# Openbook.net
KiCad netlist of a schematic drawn in EAGLE
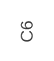
[diagram p0: schematic, sheet 1, part 1 of 2]
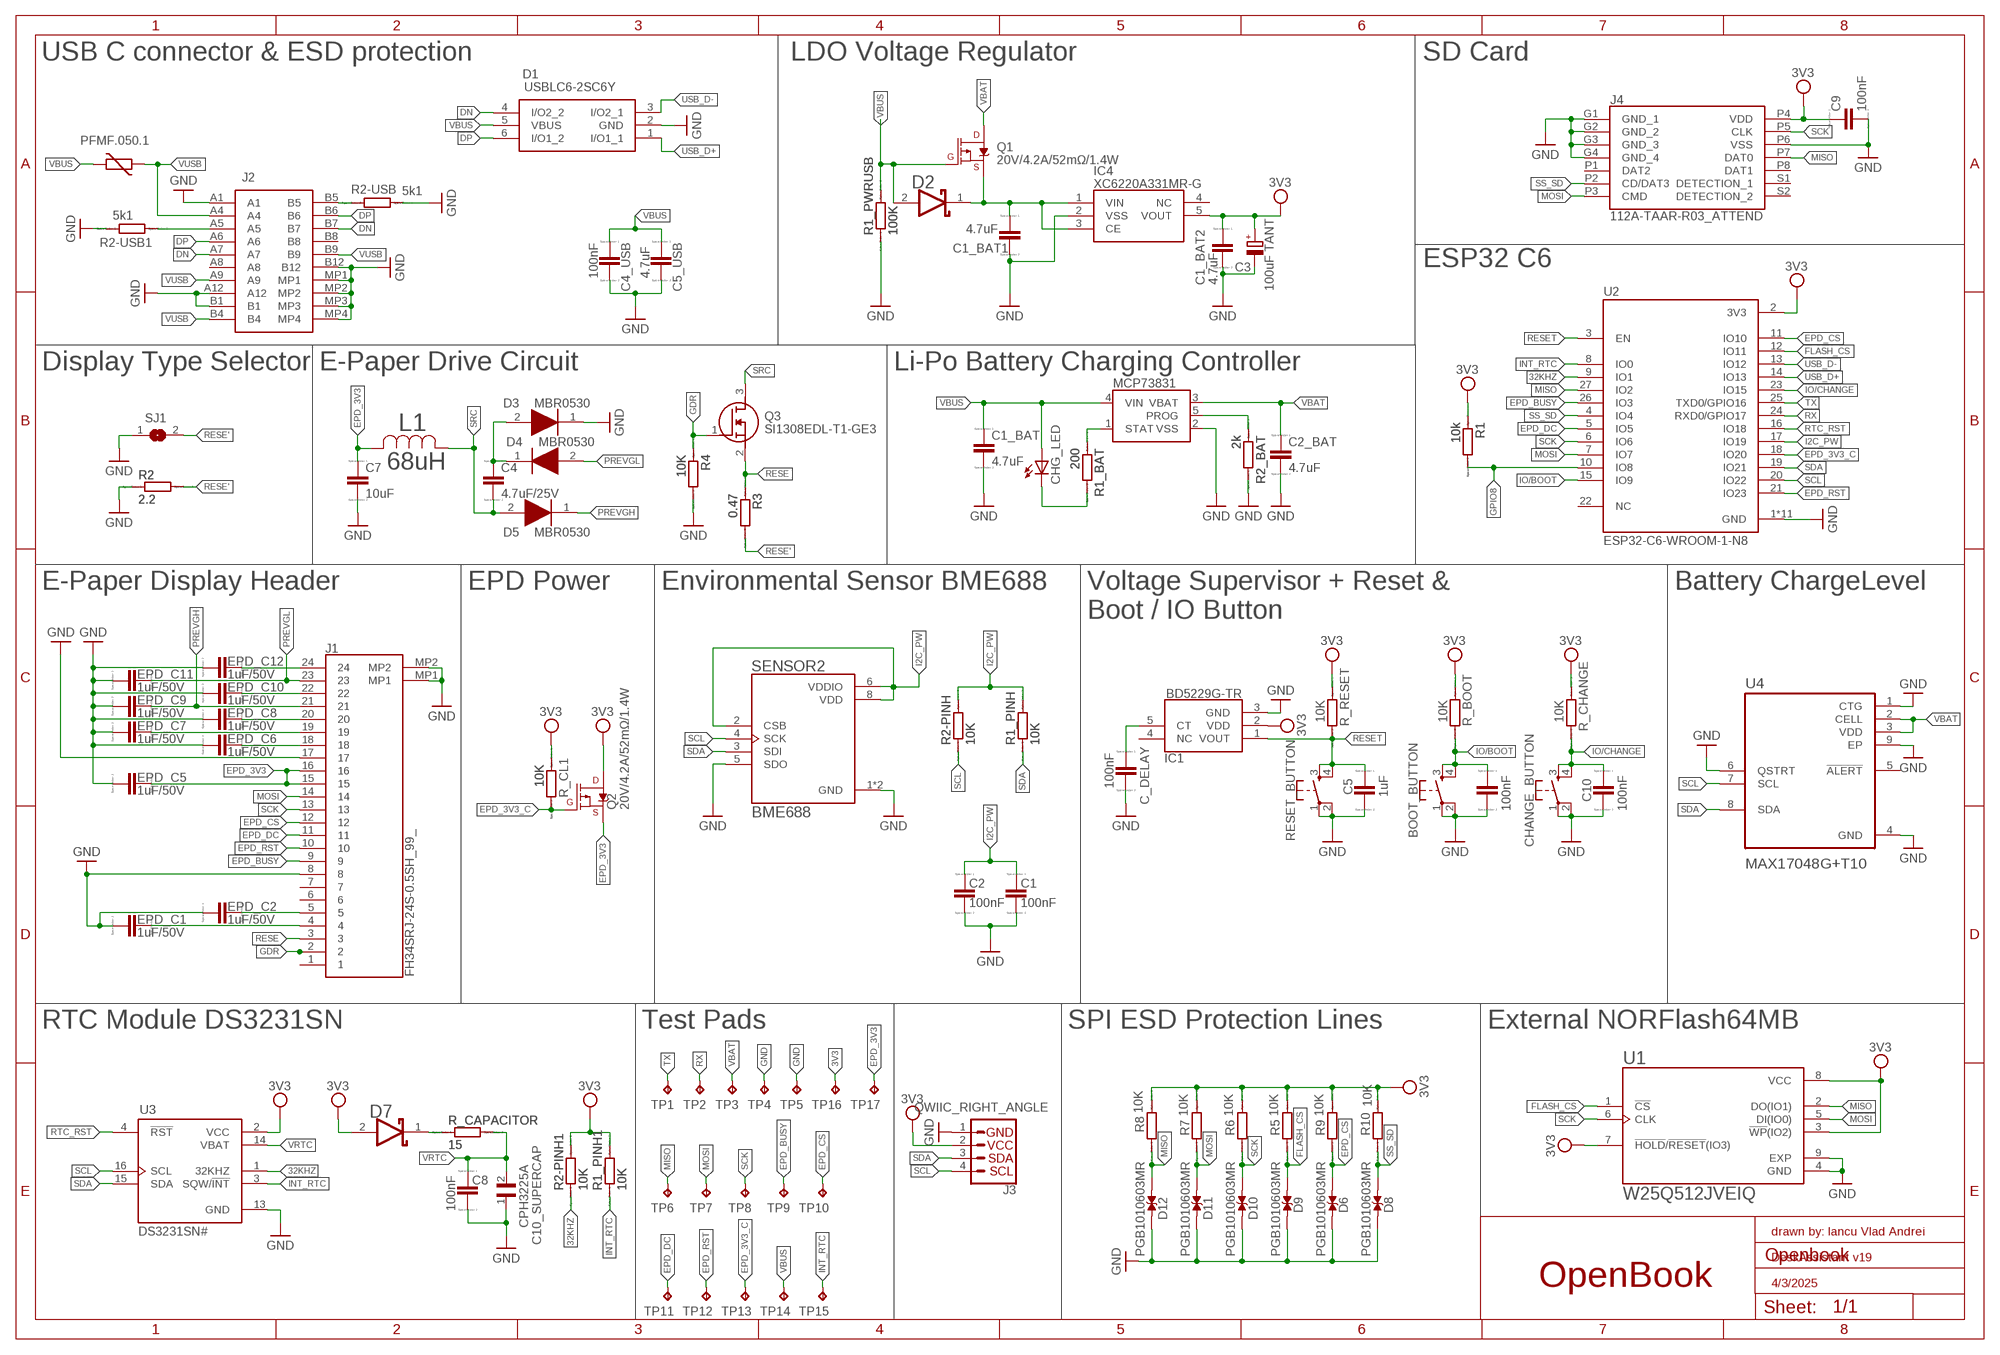
[diagram p1: schematic, sheet 1, part 2 of 2]

(export (version "E")
  (design (tool "Eeschema 10.0.6"))
  (components
    (comp (ref "BOOT_BUTTON")
      (value "BUTTON_CUSYOMV1")
      (footprint "eagle-import:MYBUTTON")
      (libsource (lib "eagle-import") (part "BUTTON_CUSYOMV1"))
    )
    (comp (ref "C1")
      (value "100nF")
      (footprint "eagle-import:EAGLE-LTSPICE_C0402")
      (libsource (lib "eagle-import") (part "EAGLE-LTSPICE_CC0402"))
    )
    (comp (ref "C1_BAT")
      (value "4.7uF")
      (footprint "eagle-import:EAGLE-LTSPICE_C0402")
      (libsource (lib "eagle-import") (part "EAGLE-LTSPICE_CC0402"))
    )
    (comp (ref "C1_BAT1")
      (value "4.7uF")
      (footprint "eagle-import:EAGLE-LTSPICE_C0402")
      (libsource (lib "eagle-import") (part "EAGLE-LTSPICE_CC0402"))
    )
    (comp (ref "C1_BAT2")
      (value "4.7uF")
      (footprint "eagle-import:EAGLE-LTSPICE_C0402")
      (libsource (lib "eagle-import") (part "EAGLE-LTSPICE_CC0402"))
    )
    (comp (ref "C2")
      (value "100nF")
      (footprint "eagle-import:EAGLE-LTSPICE_C0402")
      (libsource (lib "eagle-import") (part "EAGLE-LTSPICE_CC0402"))
    )
    (comp (ref "C2_BAT")
      (value "4.7uF")
      (footprint "eagle-import:EAGLE-LTSPICE_C0402")
      (libsource (lib "eagle-import") (part "EAGLE-LTSPICE_CC0402"))
    )
    (comp (ref "C3")
      (value "100uF TANT")
      (footprint "eagle-import:RCL_CT3528")
      (libsource (lib "eagle-import") (part "RCL_CPOL-EUCT3528"))
    )
    (comp (ref "C4")
      (value "4.7uF/25V")
      (footprint "eagle-import:EAGLE-LTSPICE_C0402")
      (libsource (lib "eagle-import") (part "EAGLE-LTSPICE_CC0402"))
    )
    (comp (ref "C4_USB")
      (value "100nF")
      (footprint "eagle-import:EAGLE-LTSPICE_C0402")
      (libsource (lib "eagle-import") (part "EAGLE-LTSPICE_CC0402"))
    )
    (comp (ref "C5")
      (value "1uF")
      (footprint "eagle-import:EAGLE-LTSPICE_C0402")
      (libsource (lib "eagle-import") (part "EAGLE-LTSPICE_CC0402"))
    )
    (comp (ref "C5_USB")
      (value "4.7uF")
      (footprint "eagle-import:EAGLE-LTSPICE_C0402")
      (libsource (lib "eagle-import") (part "EAGLE-LTSPICE_CC0402"))
    )
    (comp (ref "C6")
      (value "100nF")
      (footprint "eagle-import:EAGLE-LTSPICE_C0402")
      (libsource (lib "eagle-import") (part "EAGLE-LTSPICE_CC0402"))
    )
    (comp (ref "C7")
      (value "10uF")
      (footprint "eagle-import:EAGLE-LTSPICE_C0402")
      (libsource (lib "eagle-import") (part "EAGLE-LTSPICE_CC0402"))
    )
    (comp (ref "C8")
      (value "100nF")
      (footprint "eagle-import:EAGLE-LTSPICE_C0402")
      (libsource (lib "eagle-import") (part "EAGLE-LTSPICE_CC0402"))
    )
    (comp (ref "C9")
      (value "100nF")
      (footprint "eagle-import:EAGLE-LTSPICE_C0402")
      (libsource (lib "eagle-import") (part "EAGLE-LTSPICE_CC0402"))
    )
    (comp (ref "C10")
      (value "100nF")
      (footprint "eagle-import:EAGLE-LTSPICE_C0402")
      (libsource (lib "eagle-import") (part "EAGLE-LTSPICE_CC0402"))
    )
    (comp (ref "C10_SUPERCAP")
      (value "CPH3225A")
      (footprint "eagle-import:CAPCP3225X100N")
      (fields (field (name "MF") "Seiko Instruments"))
      (libsource (lib "eagle-import") (part "CPH3225A"))
    )
    (comp (ref "CHANGE_BUTTON")
      (value "BUTTON_CUSYOMV1")
      (footprint "eagle-import:MYBUTTON")
      (libsource (lib "eagle-import") (part "BUTTON_CUSYOMV1"))
    )
    (comp (ref "CHG_LED")
      (value "ADAFRUIT_LEDCHIP-LED0603")
      (footprint "eagle-import:ADAFRUIT_CHIP-LED0603")
      (libsource (lib "eagle-import") (part "ADAFRUIT_LEDCHIP-LED0603"))
    )
    (comp (ref "C_DELAY")
      (value "100nF")
      (footprint "eagle-import:EAGLE-LTSPICE_C0402")
      (libsource (lib "eagle-import") (part "EAGLE-LTSPICE_CC0402"))
    )
    (comp (ref "D1")
      (value "USBLC6-2SC6Y")
      (footprint "eagle-import:SOT95P280X145-6N")
      (fields (field (name "MF") "STMicroelectronics"))
      (libsource (lib "eagle-import") (part "USBLC6-2SC6Y"))
    )
    (comp (ref "D2")
      (value "SD0805S020S1R0")
      (footprint "eagle-import:ESP32_WROVER_AVX---SD0805S020S1R0_AVX_SD0805S020S1R0_0")
      (fields
        (field (name "DIGIKEY_PART_NUMBER") "478-7800-1-ND")
        (field (name "MF") "AVX")
        (field (name "MOUSER_PART_NUMBER") "581-SD0805S020S1R0")
      )
      (libsource (lib "eagle-import") (part "ESP32_WROVER_AVX---SD0805S020S1R0_AVX_SD0805S020S1R0_0_0AVX_SD0805S020S1R0_0_0"))
    )
    (comp (ref "D3")
      (value "MBR0530")
      (footprint "eagle-import:SOD3716X135N")
      (fields (field (name "MF") "ON Semiconductor"))
      (libsource (lib "eagle-import") (part "MBR0530"))
    )
    (comp (ref "D4")
      (value "MBR0530")
      (footprint "eagle-import:SOD3716X135N")
      (fields (field (name "MF") "ON Semiconductor"))
      (libsource (lib "eagle-import") (part "MBR0530"))
    )
    (comp (ref "D5")
      (value "MBR0530")
      (footprint "eagle-import:SOD3716X135N")
      (fields (field (name "MF") "ON Semiconductor"))
      (libsource (lib "eagle-import") (part "MBR0530"))
    )
    (comp (ref "D6")
      (value "PGB1010603MR")
      (footprint "eagle-import:DIOC1608X36N")
      (fields (field (name "MF") "Littelfuse Inc."))
      (libsource (lib "eagle-import") (part "PGB1010603MR"))
    )
    (comp (ref "D7")
      (value "SD0805S020S1R0")
      (footprint "eagle-import:ESP32_WROVER_AVX---SD0805S020S1R0_AVX_SD0805S020S1R0_0")
      (fields
        (field (name "DIGIKEY_PART_NUMBER") "478-7800-1-ND")
        (field (name "MF") "AVX")
        (field (name "MOUSER_PART_NUMBER") "581-SD0805S020S1R0")
      )
      (libsource (lib "eagle-import") (part "ESP32_WROVER_AVX---SD0805S020S1R0_AVX_SD0805S020S1R0_0_0AVX_SD0805S020S1R0_0_0"))
    )
    (comp (ref "D8")
      (value "PGB1010603MR")
      (footprint "eagle-import:DIOC1608X36N")
      (fields (field (name "MF") "Littelfuse Inc."))
      (libsource (lib "eagle-import") (part "PGB1010603MR"))
    )
    (comp (ref "D9")
      (value "PGB1010603MR")
      (footprint "eagle-import:DIOC1608X36N")
      (fields (field (name "MF") "Littelfuse Inc."))
      (libsource (lib "eagle-import") (part "PGB1010603MR"))
    )
    (comp (ref "D10")
      (value "PGB1010603MR")
      (footprint "eagle-import:DIOC1608X36N")
      (fields (field (name "MF") "Littelfuse Inc."))
      (libsource (lib "eagle-import") (part "PGB1010603MR"))
    )
    (comp (ref "D11")
      (value "PGB1010603MR")
      (footprint "eagle-import:DIOC1608X36N")
      (fields (field (name "MF") "Littelfuse Inc."))
      (libsource (lib "eagle-import") (part "PGB1010603MR"))
    )
    (comp (ref "D12")
      (value "PGB1010603MR")
      (footprint "eagle-import:DIOC1608X36N")
      (fields (field (name "MF") "Littelfuse Inc."))
      (libsource (lib "eagle-import") (part "PGB1010603MR"))
    )
    (comp (ref "EPD_C1")
      (value "1uF/50V")
      (footprint "eagle-import:EAGLE-LTSPICE_C0402")
      (libsource (lib "eagle-import") (part "EAGLE-LTSPICE_CC0402"))
    )
    (comp (ref "EPD_C2")
      (value "1uF/50V")
      (footprint "eagle-import:EAGLE-LTSPICE_C0402")
      (libsource (lib "eagle-import") (part "EAGLE-LTSPICE_CC0402"))
    )
    (comp (ref "EPD_C5")
      (value "1uF/50V")
      (footprint "eagle-import:EAGLE-LTSPICE_C0402")
      (libsource (lib "eagle-import") (part "EAGLE-LTSPICE_CC0402"))
    )
    (comp (ref "EPD_C6")
      (value "1uF/50V")
      (footprint "eagle-import:EAGLE-LTSPICE_C0402")
      (libsource (lib "eagle-import") (part "EAGLE-LTSPICE_CC0402"))
    )
    (comp (ref "EPD_C7")
      (value "1uF/50V")
      (footprint "eagle-import:EAGLE-LTSPICE_C0402")
      (libsource (lib "eagle-import") (part "EAGLE-LTSPICE_CC0402"))
    )
    (comp (ref "EPD_C8")
      (value "1uF/50V")
      (footprint "eagle-import:EAGLE-LTSPICE_C0402")
      (libsource (lib "eagle-import") (part "EAGLE-LTSPICE_CC0402"))
    )
    (comp (ref "EPD_C9")
      (value "1uF/50V")
      (footprint "eagle-import:EAGLE-LTSPICE_C0402")
      (libsource (lib "eagle-import") (part "EAGLE-LTSPICE_CC0402"))
    )
    (comp (ref "EPD_C10")
      (value "1uF/50V")
      (footprint "eagle-import:EAGLE-LTSPICE_C0402")
      (libsource (lib "eagle-import") (part "EAGLE-LTSPICE_CC0402"))
    )
    (comp (ref "EPD_C11")
      (value "1uF/50V")
      (footprint "eagle-import:EAGLE-LTSPICE_C0402")
      (libsource (lib "eagle-import") (part "EAGLE-LTSPICE_CC0402"))
    )
    (comp (ref "EPD_C12")
      (value "1uF/50V")
      (footprint "eagle-import:EAGLE-LTSPICE_C0402")
      (libsource (lib "eagle-import") (part "EAGLE-LTSPICE_CC0402"))
    )
    (comp (ref "IC1")
      (value "BD5229G-TR")
      (footprint "eagle-import:SOT95P280X125-5N")
      (fields (field (name "MOUSER_PART_NUMBER") "755-BD5229G-TR"))
      (libsource (lib "eagle-import") (part "BD5229G-TR"))
    )
    (comp (ref "IC4")
      (value "XC6220A331MR-G")
      (footprint "eagle-import:SOT95P280X120-5N")
      (fields (field (name "MOUSER_PART_NUMBER") "865-XC6220A331MR-G"))
      (libsource (lib "eagle-import") (part "XC6220A331MR-G"))
    )
    (comp (ref "J1")
      (value "FH34SRJ-24S-0.5SH_99_")
      (footprint "eagle-import:FH34SRJ24S05SH99")
      (fields
        (field (name "MANUFACTURER_PART_NUMBER") "FH34SRJ-24S-0.5SH(99)")
        (field (name "MOUSER_PART_NUMBER") "798-FH34SRJ24S05SH99")
      )
      (libsource (lib "eagle-import") (part "FH34SRJ-24S-0.5SH_99_"))
    )
    (comp (ref "J2")
      (value "SAMACSYS_PARTS_USB4110-GF-A")
      (footprint "eagle-import:SAMACSYS_PARTS_USB4110GFA")
      (fields
        (field (name "MANUFACTURER_PART_NUMBER") "USB4110-GF-A")
        (field (name "MOUSER_PART_NUMBER") "640-USB4110-GF-A")
      )
      (libsource (lib "eagle-import") (part "SAMACSYS_PARTS_USB4110-GF-A"))
    )
    (comp (ref "J3")
      (value "QWIIC_RIGHT_ANGLE")
      (footprint "eagle-import:JST04_1MM_RA")
      (libsource (lib "eagle-import") (part "QWIIC_CONNECTORJS-1MM"))
    )
    (comp (ref "J4")
      (value "112A-TAAR-R03_ATTEND")
      (footprint "eagle-import:112ATAARR03ATTEND")
      (fields (field (name "MANUFACTURER_PART_NUMBER") "112A-TAAR-R03 ATTEND"))
      (libsource (lib "eagle-import") (part "112A-TAAR-R03_ATTEND"))
    )
    (comp (ref "L1")
      (value "68uH")
      (footprint "eagle-import:IND_4828-WE-TPC_WRE")
      (fields
        (field (name "MANUFACTURER_PART_NUMBER") "744043680")
        (field (name "COPYRIGHT") "Copyright (C) 2024 Ultra Librarian. All rights reserved.")
      )
      (libsource (lib "eagle-import") (part "744043680IND_4828-WE-TPC_WRE"))
    )
    (comp (ref "MCP73831")
      (value "ESP32_WROVER_SPARKFUN-IC-POWER_MCP73831")
      (footprint "eagle-import:ESP32_WROVER_SPARKFUN-IC-POWER_SOT23-5")
      (libsource (lib "eagle-import") (part "ESP32_WROVER_SPARKFUN-IC-POWER_MCP73831"))
    )
    (comp (ref "PFMF.050.1")
      (value "ESP32C6_VARISTORCN1812")
      (footprint "eagle-import:ESP32C6_VARISTOR_CT_CN1812")
      (libsource (lib "eagle-import") (part "ESP32C6_VARISTORCN1812"))
    )
    (comp (ref "Q1")
      (value "20V/4.2A/52mΩ/1.4W")
      (footprint "eagle-import:ESP32_WROVER_SPARKFUN-DISCRETESEMI_SOT23-3")
      (libsource (lib "eagle-import") (part "ESP32_WROVER_SPARKFUN-DISCRETESEMI_MOSFET_PCH-DMG2305UX-7"))
    )
    (comp (ref "Q2")
      (value "20V/4.2A/52mΩ/1.4W")
      (footprint "eagle-import:ESP32_WROVER_SPARKFUN-DISCRETESEMI_SOT23-3")
      (libsource (lib "eagle-import") (part "ESP32_WROVER_SPARKFUN-DISCRETESEMI_MOSFET_PCH-DMG2305UX-7"))
    )
    (comp (ref "Q3")
      (value "SI1308EDL-T1-GE3")
      (footprint "eagle-import:SOT65P210X110-3N")
      (fields (field (name "MF") "Vishay Siliconix"))
      (libsource (lib "eagle-import") (part "SI1308EDL-T1-GE3"))
    )
    (comp (ref "R1")
      (value "10k")
      (footprint "eagle-import:ESP32_WROVER_EAGLE-LTSPICE_R0402")
      (libsource (lib "eagle-import") (part "ESP32_WROVER_EAGLE-LTSPICE_RR0402"))
    )
    (comp (ref "R1_BAT")
      (value "200")
      (footprint "eagle-import:ESP32_WROVER_EAGLE-LTSPICE_R0402")
      (libsource (lib "eagle-import") (part "ESP32_WROVER_EAGLE-LTSPICE_RR0402"))
    )
    (comp (ref "R1_PINH")
      (value "10K")
      (footprint "eagle-import:ESP32_WROVER_EAGLE-LTSPICE_R0402")
      (libsource (lib "eagle-import") (part "ESP32_WROVER_EAGLE-LTSPICE_RR0402"))
    )
    (comp (ref "R1_PINH1")
      (value "10K")
      (footprint "eagle-import:ESP32_WROVER_EAGLE-LTSPICE_R0402")
      (libsource (lib "eagle-import") (part "ESP32_WROVER_EAGLE-LTSPICE_RR0402"))
    )
    (comp (ref "R1_PWRUSB")
      (value "100K")
      (footprint "eagle-import:ESP32_WROVER_EAGLE-LTSPICE_R0402")
      (libsource (lib "eagle-import") (part "ESP32_WROVER_EAGLE-LTSPICE_RR0402"))
    )
    (comp (ref "R2")
      (value "2.2")
      (footprint "eagle-import:ESP32_WROVER_EAGLE-LTSPICE_R0402")
      (libsource (lib "eagle-import") (part "ESP32_WROVER_EAGLE-LTSPICE_RR0402"))
    )
    (comp (ref "R2-PINH")
      (value "10K")
      (footprint "eagle-import:ESP32_WROVER_EAGLE-LTSPICE_R0402")
      (libsource (lib "eagle-import") (part "ESP32_WROVER_EAGLE-LTSPICE_RR0402"))
    )
    (comp (ref "R2-PINH1")
      (value "10K")
      (footprint "eagle-import:ESP32_WROVER_EAGLE-LTSPICE_R0402")
      (libsource (lib "eagle-import") (part "ESP32_WROVER_EAGLE-LTSPICE_RR0402"))
    )
    (comp (ref "R2-USB")
      (value "5k1")
      (footprint "eagle-import:ESP32_WROVER_EAGLE-LTSPICE_R0402")
      (libsource (lib "eagle-import") (part "ESP32_WROVER_EAGLE-LTSPICE_RR0402"))
    )
    (comp (ref "R2-USB1")
      (value "5k1")
      (footprint "eagle-import:ESP32_WROVER_EAGLE-LTSPICE_R0402")
      (libsource (lib "eagle-import") (part "ESP32_WROVER_EAGLE-LTSPICE_RR0402"))
    )
    (comp (ref "R2_BAT")
      (value "2k")
      (footprint "eagle-import:ESP32_WROVER_EAGLE-LTSPICE_R0402")
      (libsource (lib "eagle-import") (part "ESP32_WROVER_EAGLE-LTSPICE_RR0402"))
    )
    (comp (ref "R3")
      (value "0.47")
      (footprint "eagle-import:ESP32_WROVER_EAGLE-LTSPICE_R0402")
      (libsource (lib "eagle-import") (part "ESP32_WROVER_EAGLE-LTSPICE_RR0402"))
    )
    (comp (ref "R4")
      (value "10K")
      (footprint "eagle-import:ESP32_WROVER_EAGLE-LTSPICE_R0402")
      (libsource (lib "eagle-import") (part "ESP32_WROVER_EAGLE-LTSPICE_RR0402"))
    )
    (comp (ref "R5")
      (value "10K")
      (footprint "eagle-import:ESP32_WROVER_EAGLE-LTSPICE_R0402")
      (libsource (lib "eagle-import") (part "ESP32_WROVER_EAGLE-LTSPICE_RR0402"))
    )
    (comp (ref "R6")
      (value "10K")
      (footprint "eagle-import:ESP32_WROVER_EAGLE-LTSPICE_R0402")
      (libsource (lib "eagle-import") (part "ESP32_WROVER_EAGLE-LTSPICE_RR0402"))
    )
    (comp (ref "R7")
      (value "10K")
      (footprint "eagle-import:ESP32_WROVER_EAGLE-LTSPICE_R0402")
      (libsource (lib "eagle-import") (part "ESP32_WROVER_EAGLE-LTSPICE_RR0402"))
    )
    (comp (ref "R8")
      (value "10K")
      (footprint "eagle-import:ESP32_WROVER_EAGLE-LTSPICE_R0402")
      (libsource (lib "eagle-import") (part "ESP32_WROVER_EAGLE-LTSPICE_RR0402"))
    )
    (comp (ref "R9")
      (value "10K")
      (footprint "eagle-import:ESP32_WROVER_EAGLE-LTSPICE_R0402")
      (libsource (lib "eagle-import") (part "ESP32_WROVER_EAGLE-LTSPICE_RR0402"))
    )
    (comp (ref "R10")
      (value "10K")
      (footprint "eagle-import:ESP32_WROVER_EAGLE-LTSPICE_R0402")
      (libsource (lib "eagle-import") (part "ESP32_WROVER_EAGLE-LTSPICE_RR0402"))
    )
    (comp (ref "RESET_BUTTON")
      (value "BUTTON_CUSYOMV1")
      (footprint "eagle-import:MYBUTTON")
      (libsource (lib "eagle-import") (part "BUTTON_CUSYOMV1"))
    )
    (comp (ref "R_BOOT")
      (value "10K")
      (footprint "eagle-import:ESP32_WROVER_EAGLE-LTSPICE_R0402")
      (libsource (lib "eagle-import") (part "ESP32_WROVER_EAGLE-LTSPICE_RR0402"))
    )
    (comp (ref "R_CAPACITOR")
      (value "15")
      (footprint "eagle-import:ESP32_WROVER_EAGLE-LTSPICE_R0402")
      (libsource (lib "eagle-import") (part "ESP32_WROVER_EAGLE-LTSPICE_RR0402"))
    )
    (comp (ref "R_CHANGE")
      (value "10K")
      (footprint "eagle-import:ESP32_WROVER_EAGLE-LTSPICE_R0402")
      (libsource (lib "eagle-import") (part "ESP32_WROVER_EAGLE-LTSPICE_RR0402"))
    )
    (comp (ref "R_CL1")
      (value "10K")
      (footprint "eagle-import:ESP32_WROVER_EAGLE-LTSPICE_R0402")
      (libsource (lib "eagle-import") (part "ESP32_WROVER_EAGLE-LTSPICE_RR0402"))
    )
    (comp (ref "R_RESET")
      (value "10K")
      (footprint "eagle-import:ESP32_WROVER_EAGLE-LTSPICE_R0402")
      (libsource (lib "eagle-import") (part "ESP32_WROVER_EAGLE-LTSPICE_RR0402"))
    )
    (comp (ref "SENSOR2")
      (value "BME688")
      (footprint "eagle-import:ESP32_WROVER_BME680_PSON80P300X300X100-8N")
      (fields (field (name "MF") "Bosch Sensortec") (field (name "MP") "BME680"))
      (libsource (lib "eagle-import") (part "ESP32_WROVER_BME680_BME680"))
    )
    (comp (ref "SJ1")
      (value "SJ")
      (footprint "eagle-import:ESP32_WROVER_EAGLE-LTSPICE_R0402")
      (libsource (lib "eagle-import") (part "SJ"))
    )
    (comp (ref "TP1")
      (value "TPTP20R")
      (footprint "eagle-import:TP20R")
      (libsource (lib "eagle-import") (part "TPTP20R"))
    )
    (comp (ref "TP2")
      (value "TPTP20R")
      (footprint "eagle-import:TP20R")
      (libsource (lib "eagle-import") (part "TPTP20R"))
    )
    (comp (ref "TP3")
      (value "TPTP20R")
      (footprint "eagle-import:TP20R")
      (libsource (lib "eagle-import") (part "TPTP20R"))
    )
    (comp (ref "TP4")
      (value "TPTP20R")
      (footprint "eagle-import:TP20R")
      (libsource (lib "eagle-import") (part "TPTP20R"))
    )
    (comp (ref "TP5")
      (value "TPTP20R")
      (footprint "eagle-import:TP20R")
      (libsource (lib "eagle-import") (part "TPTP20R"))
    )
    (comp (ref "TP6")
      (value "TPTP20R")
      (footprint "eagle-import:TP20R")
      (libsource (lib "eagle-import") (part "TPTP20R"))
    )
    (comp (ref "TP7")
      (value "TPTP20R")
      (footprint "eagle-import:TP20R")
      (libsource (lib "eagle-import") (part "TPTP20R"))
    )
    (comp (ref "TP8")
      (value "TPTP20R")
      (footprint "eagle-import:TP20R")
      (libsource (lib "eagle-import") (part "TPTP20R"))
    )
    (comp (ref "TP9")
      (value "TPTP20R")
      (footprint "eagle-import:TP20R")
      (libsource (lib "eagle-import") (part "TPTP20R"))
    )
    (comp (ref "TP10")
      (value "TPTP20R")
      (footprint "eagle-import:TP20R")
      (libsource (lib "eagle-import") (part "TPTP20R"))
    )
    (comp (ref "TP11")
      (value "TPTP20R")
      (footprint "eagle-import:TP20R")
      (libsource (lib "eagle-import") (part "TPTP20R"))
    )
    (comp (ref "TP12")
      (value "TPTP20R")
      (footprint "eagle-import:TP20R")
      (libsource (lib "eagle-import") (part "TPTP20R"))
    )
    (comp (ref "TP13")
      (value "TPTP20R")
      (footprint "eagle-import:TP20R")
      (libsource (lib "eagle-import") (part "TPTP20R"))
    )
    (comp (ref "TP14")
      (value "TPTP20R")
      (footprint "eagle-import:TP20R")
      (libsource (lib "eagle-import") (part "TPTP20R"))
    )
    (comp (ref "TP15")
      (value "TPTP20R")
      (footprint "eagle-import:TP20R")
      (libsource (lib "eagle-import") (part "TPTP20R"))
    )
    (comp (ref "TP16")
      (value "TPTP20R")
      (footprint "eagle-import:TP20R")
      (libsource (lib "eagle-import") (part "TPTP20R"))
    )
    (comp (ref "TP17")
      (value "TPTP20R")
      (footprint "eagle-import:TP20R")
      (libsource (lib "eagle-import") (part "TPTP20R"))
    )
    (comp (ref "U1")
      (value "W25Q512JVEIQ")
      (footprint "eagle-import:SON127P600X800X80-9N")
      (fields (field (name "MF") "Winbond Electronics"))
      (libsource (lib "eagle-import") (part "W25Q512JVEIQ"))
    )
    (comp (ref "U2")
      (value "ESP32-C6-WROOM-1-N8")
      (footprint "eagle-import:XCVR_ESP32-C6-WROOM-1-N8")
      (fields (field (name "MF") "Espressif Systems"))
      (libsource (lib "eagle-import") (part "ESP32-C6-WROOM-1-N8"))
    )
    (comp (ref "U3")
      (value "DS3231SN#")
      (footprint "eagle-import:SOIC127P1032X265-16N")
      (fields (field (name "MF") "Analog Devices"))
      (libsource (lib "eagle-import") (part "DS3231SN#"))
    )
    (comp (ref "U4")
      (value "MAX17048G+T10")
      (footprint "eagle-import:SON50P200X200X80-9N")
      (fields (field (name "MF") "Analog Devices"))
      (libsource (lib "eagle-import") (part "MAX17048G+T10"))
    )
  )
  (nets
    (net (code "1") (name "3V3") (class "Default")
      (node (ref "C1_BAT2") (pin "1") (pinfunction "1_1") (pintype "passive"))
      (node (ref "C3") (pin "+") (pinfunction "+_+") (pintype "passive"))
      (node (ref "C9") (pin "1") (pinfunction "1_1") (pintype "passive"))
      (node (ref "D7") (pin "2") (pinfunction "ANODE_2") (pintype "bidirectional"))
      (node (ref "IC1") (pin "2") (pinfunction "VDD_2") (pintype "bidirectional"))
      (node (ref "IC4") (pin "5") (pinfunction "VOUT_5") (pintype "bidirectional"))
      (node (ref "J3") (pin "2") (pinfunction "2_2") (pintype "power_in"))
      (node (ref "J4") (pin "P4") (pinfunction "VDD_P4") (pintype "bidirectional"))
      (node (ref "Q2") (pin "3") (pinfunction "D_3") (pintype "bidirectional"))
      (node (ref "R1") (pin "1") (pinfunction "1_1") (pintype "passive"))
      (node (ref "R10") (pin "2") (pinfunction "2_2") (pintype "passive"))
      (node (ref "R1_PINH1") (pin "2") (pinfunction "2_2") (pintype "passive"))
      (node (ref "R2-PINH1") (pin "2") (pinfunction "2_2") (pintype "passive"))
      (node (ref "R5") (pin "2") (pinfunction "2_2") (pintype "passive"))
      (node (ref "R6") (pin "2") (pinfunction "2_2") (pintype "passive"))
      (node (ref "R7") (pin "2") (pinfunction "2_2") (pintype "passive"))
      (node (ref "R8") (pin "2") (pinfunction "2_2") (pintype "passive"))
      (node (ref "R9") (pin "2") (pinfunction "2_2") (pintype "passive"))
      (node (ref "R_BOOT") (pin "1") (pinfunction "1_1") (pintype "passive"))
      (node (ref "R_CHANGE") (pin "1") (pinfunction "1_1") (pintype "passive"))
      (node (ref "R_CL1") (pin "1") (pinfunction "1_1") (pintype "passive"))
      (node (ref "R_RESET") (pin "1") (pinfunction "1_1") (pintype "passive"))
      (node (ref "TP16") (pin "TP") (pinfunction "TP_TP") (pintype "input"))
      (node (ref "U1") (pin "3") (pinfunction "~{WP}(IO2)_3") (pintype "bidirectional"))
      (node (ref "U1") (pin "7") (pinfunction "~{HOLD}/~{RESET}(IO3)_7") (pintype "bidirectional"))
      (node (ref "U1") (pin "8") (pinfunction "VCC_8") (pintype "power_in"))
      (node (ref "U2") (pin "2") (pinfunction "3V3_2") (pintype "power_in"))
      (node (ref "U3") (pin "2") (pinfunction "VCC_2") (pintype "power_in"))
    )
    (net (code "2") (name "32KHZ") (class "Default")
      (node (ref "R2-PINH1") (pin "1") (pinfunction "1_1") (pintype "passive"))
      (node (ref "U2") (pin "9") (pinfunction "IO1_9") (pintype "bidirectional"))
      (node (ref "U3") (pin "1") (pinfunction "32KHZ_1") (pintype "output"))
    )
    (net (code "3") (name "DN") (class "Default")
      (node (ref "D1") (pin "4") (pinfunction "I/O2_2_4") (pintype "bidirectional"))
      (node (ref "J2") (pin "A7") (pinfunction "A7_A7") (pintype "bidirectional"))
      (node (ref "J2") (pin "B7") (pinfunction "B7_B7") (pintype "bidirectional"))
    )
    (net (code "4") (name "DP") (class "Default")
      (node (ref "D1") (pin "6") (pinfunction "I/O1_2_6") (pintype "bidirectional"))
      (node (ref "J2") (pin "A6") (pinfunction "A6_A6") (pintype "bidirectional"))
      (node (ref "J2") (pin "B6") (pinfunction "B6_B6") (pintype "bidirectional"))
    )
    (net (code "5") (name "EPD_3V3") (class "Default")
      (node (ref "C7") (pin "1") (pinfunction "1_1") (pintype "passive"))
      (node (ref "EPD_C5") (pin "1") (pinfunction "1_1") (pintype "passive"))
      (node (ref "J1") (pin "15") (pinfunction "15_15") (pintype "bidirectional"))
      (node (ref "J1") (pin "16") (pinfunction "16_16") (pintype "bidirectional"))
      (node (ref "L1") (pin "2") (pinfunction "2_2") (pintype "passive"))
      (node (ref "Q2") (pin "2") (pinfunction "S_2") (pintype "bidirectional"))
      (node (ref "TP17") (pin "TP") (pinfunction "TP_TP") (pintype "input"))
    )
    (net (code "6") (name "EPD_3V3_C") (class "Default")
      (node (ref "Q2") (pin "1") (pinfunction "G_1") (pintype "bidirectional"))
      (node (ref "R_CL1") (pin "2") (pinfunction "2_2") (pintype "passive"))
      (node (ref "TP13") (pin "TP") (pinfunction "TP_TP") (pintype "input"))
      (node (ref "U2") (pin "18") (pinfunction "IO20_18") (pintype "bidirectional"))
    )
    (net (code "7") (name "EPD_BUSY") (class "Default")
      (node (ref "J1") (pin "9") (pinfunction "9_9") (pintype "bidirectional"))
      (node (ref "TP9") (pin "TP") (pinfunction "TP_TP") (pintype "input"))
      (node (ref "U2") (pin "26") (pinfunction "IO3_26") (pintype "bidirectional"))
    )
    (net (code "8") (name "EPD_CS") (class "Default")
      (node (ref "D6") (pin "1") (pinfunction "1_1") (pintype "passive"))
      (node (ref "J1") (pin "12") (pinfunction "12_12") (pintype "bidirectional"))
      (node (ref "R9") (pin "1") (pinfunction "1_1") (pintype "passive"))
      (node (ref "TP10") (pin "TP") (pinfunction "TP_TP") (pintype "input"))
      (node (ref "U2") (pin "11") (pinfunction "IO10_11") (pintype "bidirectional"))
    )
    (net (code "9") (name "EPD_DC") (class "Default")
      (node (ref "J1") (pin "11") (pinfunction "11_11") (pintype "bidirectional"))
      (node (ref "TP11") (pin "TP") (pinfunction "TP_TP") (pintype "input"))
      (node (ref "U2") (pin "5") (pinfunction "IO5_5") (pintype "bidirectional"))
    )
    (net (code "10") (name "EPD_RST") (class "Default")
      (node (ref "J1") (pin "10") (pinfunction "10_10") (pintype "bidirectional"))
      (node (ref "TP12") (pin "TP") (pinfunction "TP_TP") (pintype "input"))
      (node (ref "U2") (pin "21") (pinfunction "IO23_21") (pintype "bidirectional"))
    )
    (net (code "11") (name "FLASH_CS") (class "Default")
      (node (ref "D9") (pin "1") (pinfunction "1_1") (pintype "passive"))
      (node (ref "R5") (pin "1") (pinfunction "1_1") (pintype "passive"))
      (node (ref "U1") (pin "1") (pinfunction "~{CS}_1") (pintype "input"))
      (node (ref "U2") (pin "12") (pinfunction "IO11_12") (pintype "bidirectional"))
    )
    (net (code "12") (name "GDR") (class "Default")
      (node (ref "J1") (pin "2") (pinfunction "2_2") (pintype "bidirectional"))
      (node (ref "Q3") (pin "1") (pinfunction "G_1") (pintype "bidirectional"))
      (node (ref "R4") (pin "1") (pinfunction "1_1") (pintype "passive"))
    )
    (net (code "13") (name "GND") (class "Default")
      (node (ref "BOOT_BUTTON") (pin "1") (pinfunction "1_1") (pintype "passive"))
      (node (ref "BOOT_BUTTON") (pin "2") (pinfunction "2_2") (pintype "passive"))
      (node (ref "C1") (pin "2") (pinfunction "2_2") (pintype "passive"))
      (node (ref "C10") (pin "2") (pinfunction "2_2") (pintype "passive"))
      (node (ref "C10_SUPERCAP") (pin "1") (pinfunction "1_1") (pintype "passive"))
      (node (ref "C1_BAT") (pin "2") (pinfunction "2_2") (pintype "passive"))
      (node (ref "C1_BAT1") (pin "2") (pinfunction "2_2") (pintype "passive"))
      (node (ref "C1_BAT2") (pin "2") (pinfunction "2_2") (pintype "passive"))
      (node (ref "C2") (pin "2") (pinfunction "2_2") (pintype "passive"))
      (node (ref "C2_BAT") (pin "2") (pinfunction "2_2") (pintype "passive"))
      (node (ref "C3") (pin "-") (pinfunction "-_-") (pintype "passive"))
      (node (ref "C4_USB") (pin "2") (pinfunction "2_2") (pintype "passive"))
      (node (ref "C5") (pin "2") (pinfunction "2_2") (pintype "passive"))
      (node (ref "C5_USB") (pin "2") (pinfunction "2_2") (pintype "passive"))
      (node (ref "C6") (pin "2") (pinfunction "2_2") (pintype "passive"))
      (node (ref "C7") (pin "2") (pinfunction "2_2") (pintype "passive"))
      (node (ref "C8") (pin "2") (pinfunction "2_2") (pintype "passive"))
      (node (ref "C9") (pin "2") (pinfunction "2_2") (pintype "passive"))
      (node (ref "CHANGE_BUTTON") (pin "1") (pinfunction "1_1") (pintype "passive"))
      (node (ref "CHANGE_BUTTON") (pin "2") (pinfunction "2_2") (pintype "passive"))
      (node (ref "C_DELAY") (pin "2") (pinfunction "2_2") (pintype "passive"))
      (node (ref "D1") (pin "2") (pinfunction "GND_2") (pintype "bidirectional"))
      (node (ref "D10") (pin "2") (pinfunction "2_2") (pintype "passive"))
      (node (ref "D11") (pin "2") (pinfunction "2_2") (pintype "passive"))
      (node (ref "D12") (pin "2") (pinfunction "2_2") (pintype "passive"))
      (node (ref "D3") (pin "1") (pinfunction "K_1") (pintype "bidirectional"))
      (node (ref "D6") (pin "2") (pinfunction "2_2") (pintype "passive"))
      (node (ref "D8") (pin "2") (pinfunction "2_2") (pintype "passive"))
      (node (ref "D9") (pin "2") (pinfunction "2_2") (pintype "passive"))
      (node (ref "EPD_C1") (pin "2") (pinfunction "2_2") (pintype "passive"))
      (node (ref "EPD_C10") (pin "2") (pinfunction "2_2") (pintype "passive"))
      (node (ref "EPD_C11") (pin "2") (pinfunction "2_2") (pintype "passive"))
      (node (ref "EPD_C12") (pin "2") (pinfunction "2_2") (pintype "passive"))
      (node (ref "EPD_C2") (pin "2") (pinfunction "2_2") (pintype "passive"))
      (node (ref "EPD_C5") (pin "2") (pinfunction "2_2") (pintype "passive"))
      (node (ref "EPD_C6") (pin "2") (pinfunction "2_2") (pintype "passive"))
      (node (ref "EPD_C7") (pin "2") (pinfunction "2_2") (pintype "passive"))
      (node (ref "EPD_C8") (pin "2") (pinfunction "2_2") (pintype "passive"))
      (node (ref "EPD_C9") (pin "2") (pinfunction "2_2") (pintype "passive"))
      (node (ref "IC1") (pin "3") (pinfunction "GND_3") (pintype "bidirectional"))
      (node (ref "IC4") (pin "2") (pinfunction "VSS_2") (pintype "bidirectional"))
      (node (ref "J1") (pin "17") (pinfunction "17_17") (pintype "bidirectional"))
      (node (ref "J1") (pin "8") (pinfunction "8_8") (pintype "bidirectional"))
      (node (ref "J1") (pin "MP1") (pinfunction "MP1_MP1") (pintype "bidirectional"))
      (node (ref "J1") (pin "MP2") (pinfunction "MP2_MP2") (pintype "bidirectional"))
      (node (ref "J2") (pin "A1") (pinfunction "A1_A1") (pintype "bidirectional"))
      (node (ref "J2") (pin "A12") (pinfunction "A12_A12") (pintype "bidirectional"))
      (node (ref "J2") (pin "B1") (pinfunction "B1_B1") (pintype "bidirectional"))
      (node (ref "J2") (pin "B12") (pinfunction "B12_B12") (pintype "bidirectional"))
      (node (ref "J2") (pin "MP1") (pinfunction "MP1_MP1") (pintype "bidirectional"))
      (node (ref "J2") (pin "MP2") (pinfunction "MP2_MP2") (pintype "bidirectional"))
      (node (ref "J2") (pin "MP3") (pinfunction "MP3_MP3") (pintype "bidirectional"))
      (node (ref "J2") (pin "MP4") (pinfunction "MP4_MP4") (pintype "bidirectional"))
      (node (ref "J3") (pin "1") (pinfunction "1_1") (pintype "power_in"))
      (node (ref "J4") (pin "G1") (pinfunction "GND_1_G1") (pintype "bidirectional"))
      (node (ref "J4") (pin "G2") (pinfunction "GND_2_G2") (pintype "bidirectional"))
      (node (ref "J4") (pin "G3") (pinfunction "GND_3_G3") (pintype "bidirectional"))
      (node (ref "J4") (pin "G4") (pinfunction "GND_4_G4") (pintype "bidirectional"))
      (node (ref "J4") (pin "P6") (pinfunction "VSS_P6") (pintype "bidirectional"))
      (node (ref "MCP73831") (pin "2") (pinfunction "VSS_2") (pintype "power_in"))
      (node (ref "R1_PWRUSB") (pin "1") (pinfunction "1_1") (pintype "passive"))
      (node (ref "R2") (pin "1") (pinfunction "1_1") (pintype "passive"))
      (node (ref "R2-USB") (pin "1") (pinfunction "1_1") (pintype "passive"))
      (node (ref "R2-USB1") (pin "1") (pinfunction "1_1") (pintype "passive"))
      (node (ref "R2_BAT") (pin "2") (pinfunction "2_2") (pintype "passive"))
      (node (ref "R4") (pin "2") (pinfunction "2_2") (pintype "passive"))
      (node (ref "RESET_BUTTON") (pin "1") (pinfunction "1_1") (pintype "passive"))
      (node (ref "RESET_BUTTON") (pin "2") (pinfunction "2_2") (pintype "passive"))
      (node (ref "SENSOR2") (pin "1") (pinfunction "GND_1") (pintype "power_in"))
      (node (ref "SENSOR2") (pin "5") (pinfunction "SDO_5") (pintype "bidirectional"))
      (node (ref "SENSOR2") (pin "7") (pinfunction "GND_7") (pintype "power_in"))
      (node (ref "SJ1") (pin "1") (pinfunction "1_1") (pintype "passive"))
      (node (ref "TP4") (pin "TP") (pinfunction "TP_TP") (pintype "input"))
      (node (ref "TP5") (pin "TP") (pinfunction "TP_TP") (pintype "input"))
      (node (ref "U1") (pin "4") (pinfunction "GND_4") (pintype "power_in"))
      (node (ref "U1") (pin "9") (pinfunction "EXP_9") (pintype "passive"))
      (node (ref "U2") (pin "1") (pinfunction "GND_1") (pintype "power_in"))
      (node (ref "U2") (pin "28") (pinfunction "GND_28") (pintype "power_in"))
      (node (ref "U2") (pin "29_1") (pinfunction "GND_29_1") (pintype "power_in"))
      (node (ref "U2") (pin "29_2") (pinfunction "GND_29_2") (pintype "power_in"))
      (node (ref "U2") (pin "29_3") (pinfunction "GND_29_3") (pintype "power_in"))
      (node (ref "U2") (pin "29_4") (pinfunction "GND_29_4") (pintype "power_in"))
      (node (ref "U2") (pin "29_5") (pinfunction "GND_29_5") (pintype "power_in"))
      (node (ref "U2") (pin "29_6") (pinfunction "GND_29_6") (pintype "power_in"))
      (node (ref "U2") (pin "29_7") (pinfunction "GND_29_7") (pintype "power_in"))
      (node (ref "U2") (pin "29_8") (pinfunction "GND_29_8") (pintype "power_in"))
      (node (ref "U2") (pin "29_9") (pinfunction "GND_29_9") (pintype "power_in"))
      (node (ref "U3") (pin "13") (pinfunction "GND_13") (pintype "power_in"))
      (node (ref "U4") (pin "1") (pinfunction "CTG_1") (pintype "power_in"))
      (node (ref "U4") (pin "4") (pinfunction "GND_4") (pintype "power_in"))
      (node (ref "U4") (pin "6") (pinfunction "QSTRT_6") (pintype "input"))
      (node (ref "U4") (pin "9") (pinfunction "EP_9") (pintype "power_in"))
    )
    (net (code "14") (name "GPIO8") (class "Default")
      (node (ref "R1") (pin "2") (pinfunction "2_2") (pintype "passive"))
      (node (ref "U2") (pin "10") (pinfunction "IO8_10") (pintype "bidirectional"))
    )
    (net (code "15") (name "I2C_PW") (class "Default")
      (node (ref "C1") (pin "1") (pinfunction "1_1") (pintype "passive"))
      (node (ref "C2") (pin "1") (pinfunction "1_1") (pintype "passive"))
      (node (ref "R1_PINH") (pin "2") (pinfunction "2_2") (pintype "passive"))
      (node (ref "R2-PINH") (pin "2") (pinfunction "2_2") (pintype "passive"))
      (node (ref "SENSOR2") (pin "2") (pinfunction "CSB_2") (pintype "input"))
      (node (ref "SENSOR2") (pin "6") (pinfunction "VDDIO_6") (pintype "power_in"))
      (node (ref "SENSOR2") (pin "8") (pinfunction "VDD_8") (pintype "power_in"))
      (node (ref "U2") (pin "17") (pinfunction "IO19_17") (pintype "bidirectional"))
    )
    (net (code "16") (name "INT_RTC") (class "Default")
      (node (ref "R1_PINH1") (pin "1") (pinfunction "1_1") (pintype "passive"))
      (node (ref "TP15") (pin "TP") (pinfunction "TP_TP") (pintype "input"))
      (node (ref "U2") (pin "8") (pinfunction "IO0_8") (pintype "bidirectional"))
      (node (ref "U3") (pin "3") (pinfunction "SQW/~{INT}_3") (pintype "output"))
    )
    (net (code "17") (name "IO{slash}BOOT") (class "Default")
      (node (ref "BOOT_BUTTON") (pin "3") (pinfunction "3_3") (pintype "passive"))
      (node (ref "BOOT_BUTTON") (pin "4") (pinfunction "4_4") (pintype "passive"))
      (node (ref "C6") (pin "1") (pinfunction "1_1") (pintype "passive"))
      (node (ref "R_BOOT") (pin "2") (pinfunction "2_2") (pintype "passive"))
      (node (ref "U2") (pin "15") (pinfunction "IO9_15") (pintype "bidirectional"))
    )
    (net (code "18") (name "IO{slash}CHANGE") (class "Default")
      (node (ref "C10") (pin "1") (pinfunction "1_1") (pintype "passive"))
      (node (ref "CHANGE_BUTTON") (pin "3") (pinfunction "3_3") (pintype "passive"))
      (node (ref "CHANGE_BUTTON") (pin "4") (pinfunction "4_4") (pintype "passive"))
      (node (ref "R_CHANGE") (pin "2") (pinfunction "2_2") (pintype "passive"))
      (node (ref "U2") (pin "23") (pinfunction "IO15_23") (pintype "bidirectional"))
    )
    (net (code "19") (name "MISO") (class "Default")
      (node (ref "D12") (pin "1") (pinfunction "1_1") (pintype "passive"))
      (node (ref "J4") (pin "P7") (pinfunction "DAT0_P7") (pintype "bidirectional"))
      (node (ref "R8") (pin "1") (pinfunction "1_1") (pintype "passive"))
      (node (ref "TP6") (pin "TP") (pinfunction "TP_TP") (pintype "input"))
      (node (ref "U1") (pin "2") (pinfunction "DO(IO1)_2") (pintype "bidirectional"))
      (node (ref "U2") (pin "27") (pinfunction "IO2_27") (pintype "bidirectional"))
    )
    (net (code "20") (name "MOSI") (class "Default")
      (node (ref "D11") (pin "1") (pinfunction "1_1") (pintype "passive"))
      (node (ref "J1") (pin "14") (pinfunction "14_14") (pintype "bidirectional"))
      (node (ref "J4") (pin "P3") (pinfunction "CMD_P3") (pintype "bidirectional"))
      (node (ref "R7") (pin "1") (pinfunction "1_1") (pintype "passive"))
      (node (ref "TP7") (pin "TP") (pinfunction "TP_TP") (pintype "input"))
      (node (ref "U1") (pin "5") (pinfunction "DI(IO0)_5") (pintype "bidirectional"))
      (node (ref "U2") (pin "7") (pinfunction "IO7_7") (pintype "bidirectional"))
    )
    (net (code "21") (name "Net-(CHG_LED-PadC)") (class "Default")
      (node (ref "CHG_LED") (pin "C") (pinfunction "C_C") (pintype "passive"))
      (node (ref "R1_BAT") (pin "2") (pinfunction "2_2") (pintype "passive"))
    )
    (net (code "22") (name "Net-(D2-CATHODE)") (class "Default")
      (node (ref "C1_BAT1") (pin "1") (pinfunction "1_1") (pintype "passive"))
      (node (ref "D2") (pin "1") (pinfunction "CATHODE_1") (pintype "bidirectional"))
      (node (ref "IC4") (pin "1") (pinfunction "VIN_1") (pintype "bidirectional"))
      (node (ref "IC4") (pin "3") (pinfunction "CE_3") (pintype "bidirectional"))
      (node (ref "Q1") (pin "2") (pinfunction "S_2") (pintype "bidirectional"))
    )
    (net (code "23") (name "Net-(D3-A)") (class "Default")
      (node (ref "C4") (pin "1") (pinfunction "1_1") (pintype "passive"))
      (node (ref "D3") (pin "2") (pinfunction "A_2") (pintype "bidirectional"))
      (node (ref "D4") (pin "1") (pinfunction "K_1") (pintype "bidirectional"))
    )
    (net (code "24") (name "Net-(D7-CATHODE)") (class "Default")
      (node (ref "D7") (pin "1") (pinfunction "CATHODE_1") (pintype "bidirectional"))
      (node (ref "R_CAPACITOR") (pin "1") (pinfunction "1_1") (pintype "passive"))
    )
    (net (code "25") (name "Net-(EPD_C1-Pad1)") (class "Default")
      (node (ref "EPD_C1") (pin "1") (pinfunction "1_1") (pintype "passive"))
      (node (ref "J1") (pin "4") (pinfunction "4_4") (pintype "bidirectional"))
    )
    (net (code "26") (name "Net-(EPD_C2-Pad1)") (class "Default")
      (node (ref "EPD_C2") (pin "1") (pinfunction "1_1") (pintype "passive"))
      (node (ref "J1") (pin "5") (pinfunction "5_5") (pintype "bidirectional"))
    )
    (net (code "27") (name "Net-(EPD_C6-Pad1)") (class "Default")
      (node (ref "EPD_C6") (pin "1") (pinfunction "1_1") (pintype "passive"))
      (node (ref "J1") (pin "18") (pinfunction "18_18") (pintype "bidirectional"))
    )
    (net (code "28") (name "Net-(EPD_C7-Pad1)") (class "Default")
      (node (ref "EPD_C7") (pin "1") (pinfunction "1_1") (pintype "passive"))
      (node (ref "J1") (pin "19") (pinfunction "19_19") (pintype "bidirectional"))
    )
    (net (code "29") (name "Net-(EPD_C8-Pad1)") (class "Default")
      (node (ref "EPD_C8") (pin "1") (pinfunction "1_1") (pintype "passive"))
      (node (ref "J1") (pin "20") (pinfunction "20_20") (pintype "bidirectional"))
    )
    (net (code "30") (name "Net-(EPD_C10-Pad1)") (class "Default")
      (node (ref "EPD_C10") (pin "1") (pinfunction "1_1") (pintype "passive"))
      (node (ref "J1") (pin "22") (pinfunction "22_22") (pintype "bidirectional"))
    )
    (net (code "31") (name "Net-(EPD_C12-Pad1)") (class "Default")
      (node (ref "EPD_C12") (pin "1") (pinfunction "1_1") (pintype "passive"))
      (node (ref "J1") (pin "24") (pinfunction "24_24") (pintype "bidirectional"))
    )
    (net (code "32") (name "Net-(IC1-CT)") (class "Default")
      (node (ref "C_DELAY") (pin "1") (pinfunction "1_1") (pintype "passive"))
      (node (ref "IC1") (pin "5") (pinfunction "CT_5") (pintype "bidirectional"))
    )
    (net (code "33") (name "Net-(J2-PadA5)") (class "Default")
      (node (ref "J2") (pin "A5") (pinfunction "A5_A5") (pintype "bidirectional"))
      (node (ref "R2-USB1") (pin "2") (pinfunction "2_2") (pintype "passive"))
    )
    (net (code "34") (name "Net-(J2-PadB5)") (class "Default")
      (node (ref "J2") (pin "B5") (pinfunction "B5_B5") (pintype "bidirectional"))
      (node (ref "R2-USB") (pin "2") (pinfunction "2_2") (pintype "passive"))
    )
    (net (code "35") (name "Net-(MCP73831-PROG)") (class "Default")
      (node (ref "MCP73831") (pin "5") (pinfunction "PROG_5") (pintype "input"))
      (node (ref "R2_BAT") (pin "1") (pinfunction "1_1") (pintype "passive"))
    )
    (net (code "36") (name "Net-(MCP73831-STAT)") (class "Default")
      (node (ref "MCP73831") (pin "1") (pinfunction "STAT_1") (pintype "output"))
      (node (ref "R1_BAT") (pin "1") (pinfunction "1_1") (pintype "passive"))
    )
    (net (code "37") (name "PREVGH") (class "Default")
      (node (ref "D5") (pin "1") (pinfunction "K_1") (pintype "bidirectional"))
      (node (ref "EPD_C9") (pin "1") (pinfunction "1_1") (pintype "passive"))
      (node (ref "J1") (pin "21") (pinfunction "21_21") (pintype "bidirectional"))
    )
    (net (code "38") (name "PREVGL") (class "Default")
      (node (ref "D4") (pin "2") (pinfunction "A_2") (pintype "bidirectional"))
      (node (ref "EPD_C11") (pin "1") (pinfunction "1_1") (pintype "passive"))
      (node (ref "J1") (pin "23") (pinfunction "23_23") (pintype "bidirectional"))
    )
    (net (code "39") (name "RESE") (class "Default")
      (node (ref "J1") (pin "3") (pinfunction "3_3") (pintype "bidirectional"))
      (node (ref "Q3") (pin "2") (pinfunction "S_2") (pintype "bidirectional"))
      (node (ref "R3") (pin "1") (pinfunction "1_1") (pintype "passive"))
    )
    (net (code "40") (name "RESE'") (class "Default")
      (node (ref "R2") (pin "2") (pinfunction "2_2") (pintype "passive"))
      (node (ref "R3") (pin "2") (pinfunction "2_2") (pintype "passive"))
      (node (ref "SJ1") (pin "2") (pinfunction "2_2") (pintype "passive"))
    )
    (net (code "41") (name "RESET") (class "Default")
      (node (ref "C5") (pin "1") (pinfunction "1_1") (pintype "passive"))
      (node (ref "IC1") (pin "1") (pinfunction "VOUT_1") (pintype "bidirectional"))
      (node (ref "RESET_BUTTON") (pin "3") (pinfunction "3_3") (pintype "passive"))
      (node (ref "RESET_BUTTON") (pin "4") (pinfunction "4_4") (pintype "passive"))
      (node (ref "R_RESET") (pin "2") (pinfunction "2_2") (pintype "passive"))
      (node (ref "U2") (pin "3") (pinfunction "EN_3") (pintype "input"))
    )
    (net (code "42") (name "RTC_RST") (class "Default")
      (node (ref "U2") (pin "16") (pinfunction "IO18_16") (pintype "bidirectional"))
      (node (ref "U3") (pin "4") (pinfunction "~{RST}_4") (pintype "input"))
    )
    (net (code "43") (name "RX") (class "Default")
      (node (ref "TP2") (pin "TP") (pinfunction "TP_TP") (pintype "input"))
      (node (ref "U2") (pin "24") (pinfunction "RXD0/GPIO17_24") (pintype "bidirectional"))
    )
    (net (code "44") (name "SCK") (class "Default")
      (node (ref "D10") (pin "1") (pinfunction "1_1") (pintype "passive"))
      (node (ref "J1") (pin "13") (pinfunction "13_13") (pintype "bidirectional"))
      (node (ref "J4") (pin "P5") (pinfunction "CLK_P5") (pintype "bidirectional"))
      (node (ref "R6") (pin "1") (pinfunction "1_1") (pintype "passive"))
      (node (ref "TP8") (pin "TP") (pinfunction "TP_TP") (pintype "input"))
      (node (ref "U1") (pin "6") (pinfunction "CLK_6") (pintype "input"))
      (node (ref "U2") (pin "6") (pinfunction "IO6_6") (pintype "bidirectional"))
    )
    (net (code "45") (name "SCL") (class "Default")
      (node (ref "J3") (pin "4") (pinfunction "4_4") (pintype "passive"))
      (node (ref "R2-PINH") (pin "1") (pinfunction "1_1") (pintype "passive"))
      (node (ref "SENSOR2") (pin "4") (pinfunction "SCK_4") (pintype "input"))
      (node (ref "U2") (pin "20") (pinfunction "IO22_20") (pintype "bidirectional"))
      (node (ref "U3") (pin "16") (pinfunction "SCL_16") (pintype "input"))
      (node (ref "U4") (pin "7") (pinfunction "SCL_7") (pintype "input"))
    )
    (net (code "46") (name "SDA") (class "Default")
      (node (ref "J3") (pin "3") (pinfunction "3_3") (pintype "passive"))
      (node (ref "R1_PINH") (pin "1") (pinfunction "1_1") (pintype "passive"))
      (node (ref "SENSOR2") (pin "3") (pinfunction "SDI_3") (pintype "bidirectional"))
      (node (ref "U2") (pin "19") (pinfunction "IO21_19") (pintype "bidirectional"))
      (node (ref "U3") (pin "15") (pinfunction "SDA_15") (pintype "bidirectional"))
      (node (ref "U4") (pin "8") (pinfunction "SDA_8") (pintype "bidirectional"))
    )
    (net (code "47") (name "SRC") (class "Default")
      (node (ref "C4") (pin "2") (pinfunction "2_2") (pintype "passive"))
      (node (ref "D5") (pin "2") (pinfunction "A_2") (pintype "bidirectional"))
      (node (ref "L1") (pin "1") (pinfunction "1_1") (pintype "passive"))
      (node (ref "Q3") (pin "3") (pinfunction "D_3") (pintype "bidirectional"))
    )
    (net (code "48") (name "SS_SD") (class "Default")
      (node (ref "D8") (pin "1") (pinfunction "1_1") (pintype "passive"))
      (node (ref "J4") (pin "P2") (pinfunction "CD/DAT3_P2") (pintype "bidirectional"))
      (node (ref "R10") (pin "1") (pinfunction "1_1") (pintype "passive"))
      (node (ref "U2") (pin "4") (pinfunction "IO4_4") (pintype "bidirectional"))
    )
    (net (code "49") (name "TX") (class "Default")
      (node (ref "TP1") (pin "TP") (pinfunction "TP_TP") (pintype "input"))
      (node (ref "U2") (pin "25") (pinfunction "TXD0/GPIO16_25") (pintype "bidirectional"))
    )
    (net (code "50") (name "USB_D+") (class "Default")
      (node (ref "D1") (pin "1") (pinfunction "I/O1_1_1") (pintype "bidirectional"))
      (node (ref "U2") (pin "14") (pinfunction "IO13_14") (pintype "bidirectional"))
    )
    (net (code "51") (name "USB_D-") (class "Default")
      (node (ref "D1") (pin "3") (pinfunction "I/O2_1_3") (pintype "bidirectional"))
      (node (ref "U2") (pin "13") (pinfunction "IO12_13") (pintype "bidirectional"))
    )
    (net (code "52") (name "VBAT") (class "Default")
      (node (ref "C2_BAT") (pin "1") (pinfunction "1_1") (pintype "passive"))
      (node (ref "MCP73831") (pin "3") (pinfunction "VBAT_3") (pintype "power_in"))
      (node (ref "Q1") (pin "3") (pinfunction "D_3") (pintype "bidirectional"))
      (node (ref "TP3") (pin "TP") (pinfunction "TP_TP") (pintype "input"))
      (node (ref "U4") (pin "2") (pinfunction "CELL_2") (pintype "power_in"))
      (node (ref "U4") (pin "3") (pinfunction "VDD_3") (pintype "power_in"))
    )
    (net (code "53") (name "VBUS") (class "Default")
      (node (ref "C1_BAT") (pin "1") (pinfunction "1_1") (pintype "passive"))
      (node (ref "C4_USB") (pin "1") (pinfunction "1_1") (pintype "passive"))
      (node (ref "C5_USB") (pin "1") (pinfunction "1_1") (pintype "passive"))
      (node (ref "CHG_LED") (pin "A") (pinfunction "A_A") (pintype "passive"))
      (node (ref "D1") (pin "5") (pinfunction "VBUS_5") (pintype "bidirectional"))
      (node (ref "D2") (pin "2") (pinfunction "ANODE_2") (pintype "bidirectional"))
      (node (ref "MCP73831") (pin "4") (pinfunction "VIN_4") (pintype "power_in"))
      (node (ref "PFMF.050.1") (pin "2") (pinfunction "2_2") (pintype "passive"))
      (node (ref "Q1") (pin "1") (pinfunction "G_1") (pintype "bidirectional"))
      (node (ref "R1_PWRUSB") (pin "2") (pinfunction "2_2") (pintype "passive"))
      (node (ref "TP14") (pin "TP") (pinfunction "TP_TP") (pintype "input"))
    )
    (net (code "54") (name "VRTC") (class "Default")
      (node (ref "C10_SUPERCAP") (pin "2") (pinfunction "2_2") (pintype "passive"))
      (node (ref "C8") (pin "1") (pinfunction "1_1") (pintype "passive"))
      (node (ref "R_CAPACITOR") (pin "2") (pinfunction "2_2") (pintype "passive"))
      (node (ref "U3") (pin "14") (pinfunction "VBAT_14") (pintype "power_in"))
    )
    (net (code "55") (name "VUSB") (class "Default")
      (node (ref "J2") (pin "A4") (pinfunction "A4_A4") (pintype "bidirectional"))
      (node (ref "J2") (pin "A9") (pinfunction "A9_A9") (pintype "bidirectional"))
      (node (ref "J2") (pin "B4") (pinfunction "B4_B4") (pintype "bidirectional"))
      (node (ref "J2") (pin "B9") (pinfunction "B9_B9") (pintype "bidirectional"))
      (node (ref "PFMF.050.1") (pin "1") (pinfunction "1_1") (pintype "passive"))
    )
    (net (code "56") (name "unconnected-(IC1-NC-Pad4)") (class "Default")
      (node (ref "IC1") (pin "4") (pinfunction "NC_4") (pintype "no_connect"))
    )
    (net (code "57") (name "unconnected-(IC4-NC-Pad4)") (class "Default")
      (node (ref "IC4") (pin "4") (pinfunction "NC_4") (pintype "no_connect"))
    )
    (net (code "58") (name "unconnected-(J1-Pad1)") (class "Default")
      (node (ref "J1") (pin "1") (pinfunction "1_1") (pintype "bidirectional"))
    )
    (net (code "59") (name "unconnected-(J1-Pad6)") (class "Default")
      (node (ref "J1") (pin "6") (pinfunction "6_6") (pintype "bidirectional"))
    )
    (net (code "60") (name "unconnected-(J1-Pad7)") (class "Default")
      (node (ref "J1") (pin "7") (pinfunction "7_7") (pintype "bidirectional"))
    )
    (net (code "61") (name "unconnected-(J2-PadA8)") (class "Default")
      (node (ref "J2") (pin "A8") (pinfunction "A8_A8") (pintype "bidirectional"))
    )
    (net (code "62") (name "unconnected-(J2-PadB8)") (class "Default")
      (node (ref "J2") (pin "B8") (pinfunction "B8_B8") (pintype "bidirectional"))
    )
    (net (code "63") (name "unconnected-(J4-DAT1-PadP8)") (class "Default")
      (node (ref "J4") (pin "P8") (pinfunction "DAT1_P8") (pintype "bidirectional"))
    )
    (net (code "64") (name "unconnected-(J4-DAT2-PadP1)") (class "Default")
      (node (ref "J4") (pin "P1") (pinfunction "DAT2_P1") (pintype "bidirectional"))
    )
    (net (code "65") (name "unconnected-(J4-DETECTION_1-PadS1)") (class "Default")
      (node (ref "J4") (pin "S1") (pinfunction "DETECTION_1_S1") (pintype "bidirectional"))
    )
    (net (code "66") (name "unconnected-(J4-DETECTION_2-PadS2)") (class "Default")
      (node (ref "J4") (pin "S2") (pinfunction "DETECTION_2_S2") (pintype "bidirectional"))
    )
    (net (code "67") (name "unconnected-(U2-NC-Pad22)") (class "Default")
      (node (ref "U2") (pin "22") (pinfunction "NC_22") (pintype "no_connect"))
    )
    (net (code "68") (name "unconnected-(U4-~{ALERT}-Pad5)") (class "Default")
      (node (ref "U4") (pin "5") (pinfunction "~{ALERT}_5") (pintype "output"))
    )
  )
)
